# Red_Buggy_2015.net
KiCad netlist of a schematic drawn in EAGLE
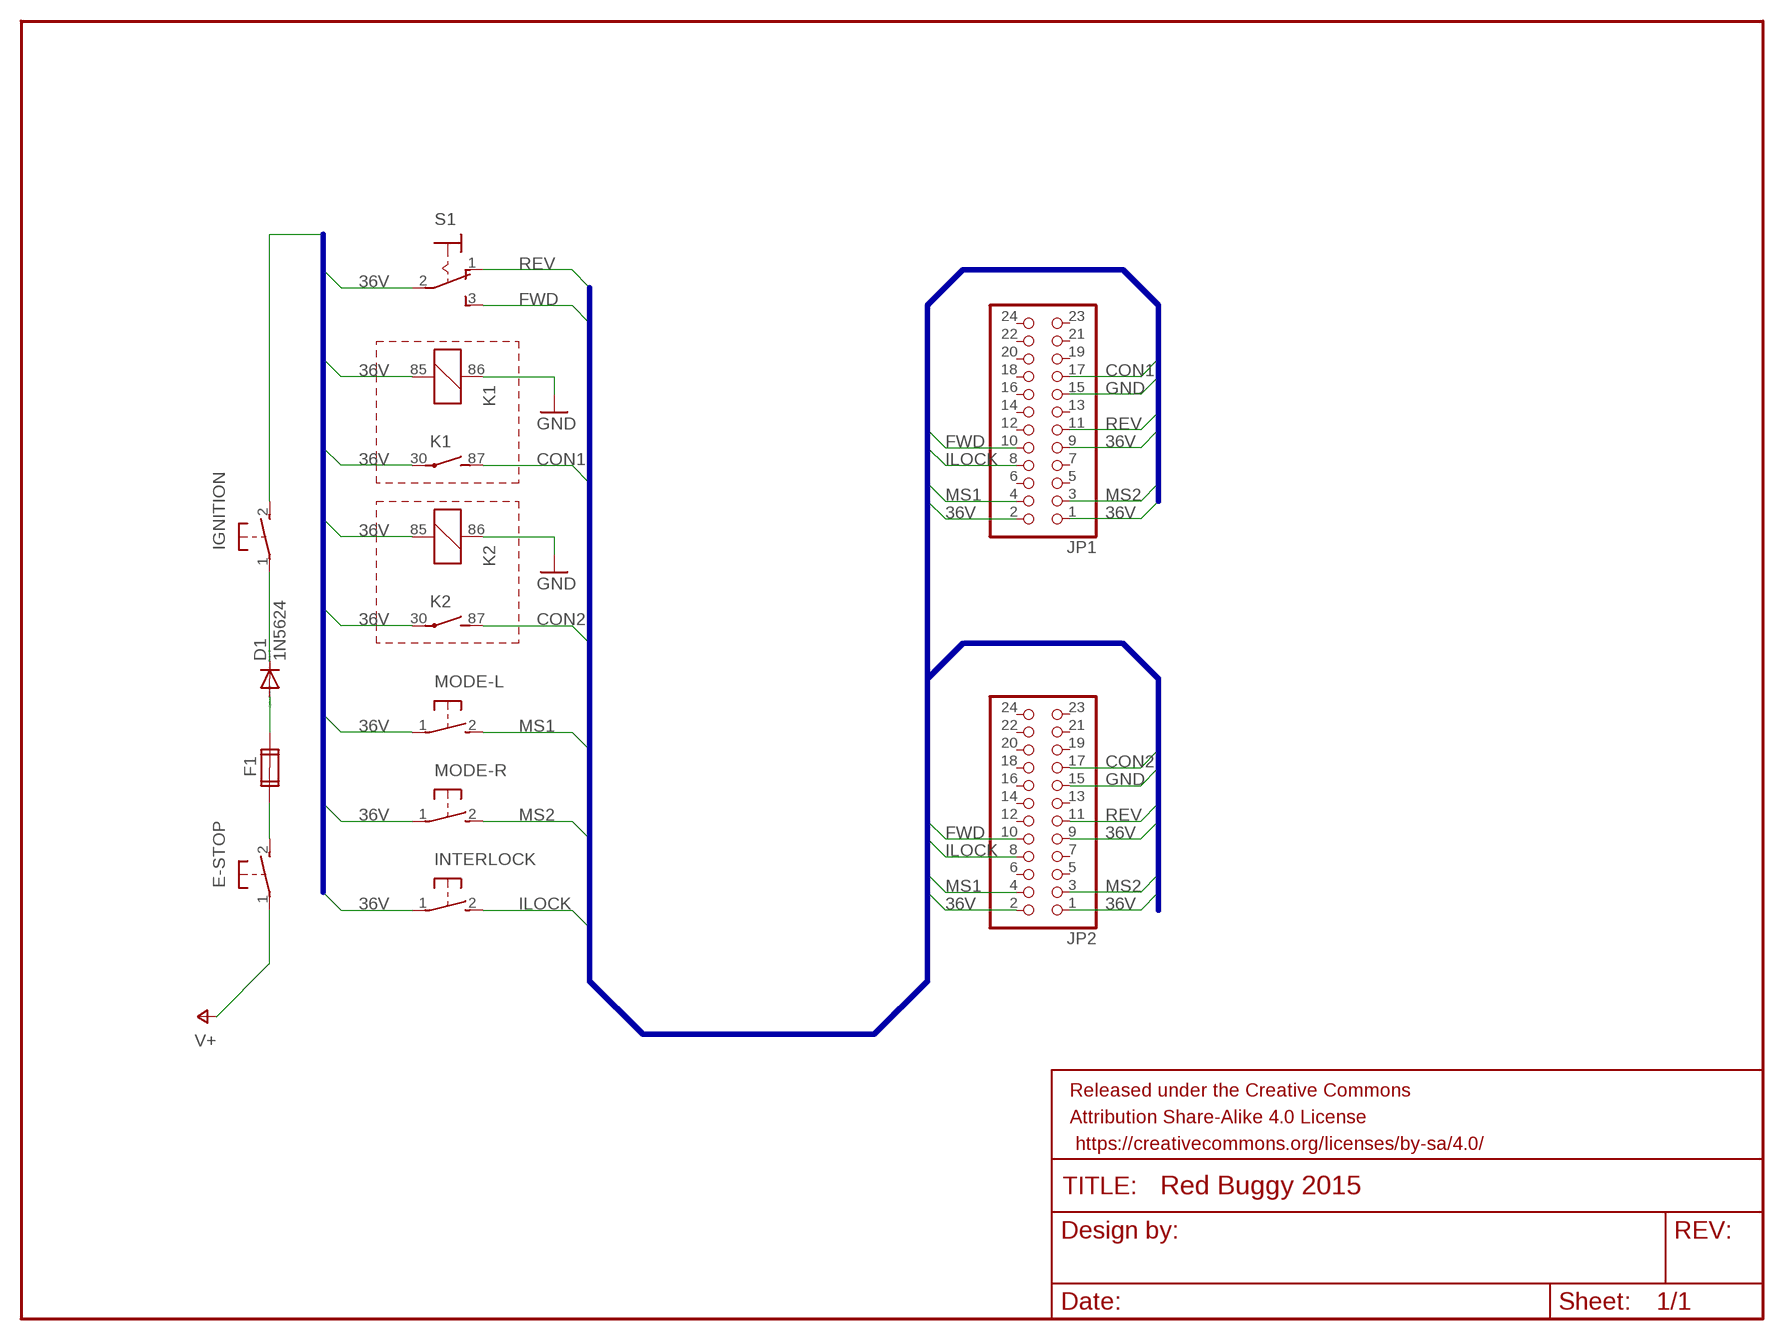
[diagram p0: schematic, sheet 1]

(export (version "E")
  (design (tool "Eeschema 10.0.6"))
  (components
    (comp (ref "D1")
      (value "1N5624")
      (footprint "eagle-import:DO201-15")
      (libsource (lib "eagle-import") (part "1N5624"))
    )
    (comp (ref "E-STOP")
      (value "31-XX")
      (footprint "eagle-import:B3F-31XX")
      (libsource (lib "eagle-import") (part "31-XX"))
    )
    (comp (ref "F1")
      (value "FUSE2P")
      (footprint "eagle-import:FUSE1")
      (libsource (lib "eagle-import") (part "FUSE2P"))
    )
    (comp (ref "FRAME1")
      (value "FRAME-LETTER")
      (footprint "eagle-import:CREATIVE_COMMONS")
      (libsource (lib "eagle-import") (part "FRAME-LETTER"))
    )
    (comp (ref "IGNITION")
      (value "31-XX")
      (footprint "eagle-import:B3F-31XX")
      (libsource (lib "eagle-import") (part "31-XX"))
    )
    (comp (ref "INTERLOCK")
      (value "31-XX")
      (footprint "eagle-import:B3F-31XX")
      (libsource (lib "eagle-import") (part "31-XX"))
    )
    (comp (ref "JP1")
      (value "PINHD-2X12")
      (footprint "eagle-import:2X12")
      (libsource (lib "eagle-import") (part "PINHD-2X12"))
    )
    (comp (ref "JP2")
      (value "PINHD-2X12")
      (footprint "eagle-import:2X12")
      (libsource (lib "eagle-import") (part "PINHD-2X12"))
    )
    (comp (ref "K1")
      (value "CB1A-P-12V")
      (footprint "eagle-import:CB1")
      (fields (field (name "MF") "AROMAT/ MATSUSHITA"))
      (libsource (lib "eagle-import") (part "CB1A-P-12V"))
    )
    (comp (ref "K2")
      (value "CB1A-P-12V")
      (footprint "eagle-import:CB1")
      (fields (field (name "MF") "AROMAT/ MATSUSHITA"))
      (libsource (lib "eagle-import") (part "CB1A-P-12V"))
    )
    (comp (ref "MODE-L")
      (value "31-XX")
      (footprint "eagle-import:B3F-31XX")
      (libsource (lib "eagle-import") (part "31-XX"))
    )
    (comp (ref "MODE-R")
      (value "31-XX")
      (footprint "eagle-import:B3F-31XX")
      (libsource (lib "eagle-import") (part "31-XX"))
    )
    (comp (ref "S1")
      (value "320-916")
      (footprint "eagle-import:320-916")
      (libsource (lib "eagle-import") (part "320-916"))
    )
  )
  (nets
    (net (code "1") (name "/36V") (class "Default")
      (node (ref "IGNITION") (pin "2") (pinfunction "S_2") (pintype "passive"))
      (node (ref "INTERLOCK") (pin "1") (pinfunction "P_1") (pintype "passive"))
      (node (ref "JP1") (pin "1") (pinfunction "1_1") (pintype "passive"))
      (node (ref "JP1") (pin "2") (pinfunction "2_2") (pintype "passive"))
      (node (ref "JP1") (pin "9") (pinfunction "9_9") (pintype "passive"))
      (node (ref "JP2") (pin "1") (pinfunction "1_1") (pintype "passive"))
      (node (ref "JP2") (pin "2") (pinfunction "2_2") (pintype "passive"))
      (node (ref "JP2") (pin "9") (pinfunction "9_9") (pintype "passive"))
      (node (ref "K1") (pin "30") (pinfunction "P_30") (pintype "passive"))
      (node (ref "K1") (pin "85") (pinfunction "2_85") (pintype "passive"))
      (node (ref "K2") (pin "30") (pinfunction "P_30") (pintype "passive"))
      (node (ref "K2") (pin "85") (pinfunction "2_85") (pintype "passive"))
      (node (ref "MODE-L") (pin "1") (pinfunction "P_1") (pintype "passive"))
      (node (ref "MODE-R") (pin "1") (pinfunction "P_1") (pintype "passive"))
      (node (ref "S1") (pin "2") (pinfunction "P_2") (pintype "passive"))
    )
    (net (code "2") (name "/CON1") (class "Default")
      (node (ref "JP1") (pin "17") (pinfunction "17_17") (pintype "passive"))
      (node (ref "K1") (pin "87") (pinfunction "S_87") (pintype "passive"))
    )
    (net (code "3") (name "/CON2") (class "Default")
      (node (ref "JP2") (pin "17") (pinfunction "17_17") (pintype "passive"))
      (node (ref "K2") (pin "87") (pinfunction "S_87") (pintype "passive"))
    )
    (net (code "4") (name "/FWD") (class "Default")
      (node (ref "JP1") (pin "10") (pinfunction "10_10") (pintype "passive"))
      (node (ref "JP2") (pin "10") (pinfunction "10_10") (pintype "passive"))
      (node (ref "S1") (pin "3") (pinfunction "S_3") (pintype "passive"))
    )
    (net (code "5") (name "/ILOCK") (class "Default")
      (node (ref "INTERLOCK") (pin "2") (pinfunction "S_2") (pintype "passive"))
      (node (ref "JP1") (pin "8") (pinfunction "8_8") (pintype "passive"))
      (node (ref "JP2") (pin "8") (pinfunction "8_8") (pintype "passive"))
    )
    (net (code "6") (name "/MS1") (class "Default")
      (node (ref "JP1") (pin "4") (pinfunction "4_4") (pintype "passive"))
      (node (ref "JP2") (pin "4") (pinfunction "4_4") (pintype "passive"))
      (node (ref "MODE-L") (pin "2") (pinfunction "S_2") (pintype "passive"))
    )
    (net (code "7") (name "/MS2") (class "Default")
      (node (ref "JP1") (pin "3") (pinfunction "3_3") (pintype "passive"))
      (node (ref "JP2") (pin "3") (pinfunction "3_3") (pintype "passive"))
      (node (ref "MODE-R") (pin "2") (pinfunction "S_2") (pintype "passive"))
    )
    (net (code "8") (name "/REV") (class "Default")
      (node (ref "JP1") (pin "11") (pinfunction "11_11") (pintype "passive"))
      (node (ref "JP2") (pin "11") (pinfunction "11_11") (pintype "passive"))
      (node (ref "S1") (pin "1") (pinfunction "O_1") (pintype "passive"))
    )
    (net (code "9") (name "GND") (class "Default")
      (node (ref "JP1") (pin "15") (pinfunction "15_15") (pintype "passive"))
      (node (ref "JP2") (pin "15") (pinfunction "15_15") (pintype "passive"))
      (node (ref "K1") (pin "86") (pinfunction "1_86") (pintype "passive"))
      (node (ref "K2") (pin "86") (pinfunction "1_86") (pintype "passive"))
    )
    (net (code "10") (name "Net-(D1-PadA)") (class "Default")
      (node (ref "D1") (pin "A") (pinfunction "A_A") (pintype "passive"))
      (node (ref "F1") (pin "2A") (pinfunction "2A_2A") (pintype "passive"))
    )
    (net (code "11") (name "Net-(E-STOP-S)") (class "Default")
      (node (ref "E-STOP") (pin "2") (pinfunction "S_2") (pintype "passive"))
      (node (ref "F1") (pin "1A") (pinfunction "1A_1A") (pintype "passive"))
    )
    (net (code "12") (name "Net-(IGNITION-P)") (class "Default")
      (node (ref "D1") (pin "C") (pinfunction "C_C") (pintype "passive"))
      (node (ref "IGNITION") (pin "1") (pinfunction "P_1") (pintype "passive"))
    )
    (net (code "13") (name "V+") (class "Default")
      (node (ref "E-STOP") (pin "1") (pinfunction "P_1") (pintype "passive"))
    )
    (net (code "14") (name "unconnected-(F1-Pad1B)") (class "Default")
      (node (ref "F1") (pin "1B") (pinfunction "1B_1B") (pintype "passive"))
    )
    (net (code "15") (name "unconnected-(F1-Pad2B)") (class "Default")
      (node (ref "F1") (pin "2B") (pinfunction "2B_2B") (pintype "passive"))
    )
    (net (code "16") (name "unconnected-(JP1-Pad5)") (class "Default")
      (node (ref "JP1") (pin "5") (pinfunction "5_5") (pintype "passive"))
    )
    (net (code "17") (name "unconnected-(JP1-Pad6)") (class "Default")
      (node (ref "JP1") (pin "6") (pinfunction "6_6") (pintype "passive"))
    )
    (net (code "18") (name "unconnected-(JP1-Pad7)") (class "Default")
      (node (ref "JP1") (pin "7") (pinfunction "7_7") (pintype "passive"))
    )
    (net (code "19") (name "unconnected-(JP1-Pad12)") (class "Default")
      (node (ref "JP1") (pin "12") (pinfunction "12_12") (pintype "passive"))
    )
    (net (code "20") (name "unconnected-(JP1-Pad13)") (class "Default")
      (node (ref "JP1") (pin "13") (pinfunction "13_13") (pintype "passive"))
    )
    (net (code "21") (name "unconnected-(JP1-Pad14)") (class "Default")
      (node (ref "JP1") (pin "14") (pinfunction "14_14") (pintype "passive"))
    )
    (net (code "22") (name "unconnected-(JP1-Pad16)") (class "Default")
      (node (ref "JP1") (pin "16") (pinfunction "16_16") (pintype "passive"))
    )
    (net (code "23") (name "unconnected-(JP1-Pad18)") (class "Default")
      (node (ref "JP1") (pin "18") (pinfunction "18_18") (pintype "passive"))
    )
    (net (code "24") (name "unconnected-(JP1-Pad19)") (class "Default")
      (node (ref "JP1") (pin "19") (pinfunction "19_19") (pintype "passive"))
    )
    (net (code "25") (name "unconnected-(JP1-Pad20)") (class "Default")
      (node (ref "JP1") (pin "20") (pinfunction "20_20") (pintype "passive"))
    )
    (net (code "26") (name "unconnected-(JP1-Pad21)") (class "Default")
      (node (ref "JP1") (pin "21") (pinfunction "21_21") (pintype "passive"))
    )
    (net (code "27") (name "unconnected-(JP1-Pad22)") (class "Default")
      (node (ref "JP1") (pin "22") (pinfunction "22_22") (pintype "passive"))
    )
    (net (code "28") (name "unconnected-(JP1-Pad23)") (class "Default")
      (node (ref "JP1") (pin "23") (pinfunction "23_23") (pintype "passive"))
    )
    (net (code "29") (name "unconnected-(JP1-Pad24)") (class "Default")
      (node (ref "JP1") (pin "24") (pinfunction "24_24") (pintype "passive"))
    )
    (net (code "30") (name "unconnected-(JP2-Pad5)") (class "Default")
      (node (ref "JP2") (pin "5") (pinfunction "5_5") (pintype "passive"))
    )
    (net (code "31") (name "unconnected-(JP2-Pad6)") (class "Default")
      (node (ref "JP2") (pin "6") (pinfunction "6_6") (pintype "passive"))
    )
    (net (code "32") (name "unconnected-(JP2-Pad7)") (class "Default")
      (node (ref "JP2") (pin "7") (pinfunction "7_7") (pintype "passive"))
    )
    (net (code "33") (name "unconnected-(JP2-Pad12)") (class "Default")
      (node (ref "JP2") (pin "12") (pinfunction "12_12") (pintype "passive"))
    )
    (net (code "34") (name "unconnected-(JP2-Pad13)") (class "Default")
      (node (ref "JP2") (pin "13") (pinfunction "13_13") (pintype "passive"))
    )
    (net (code "35") (name "unconnected-(JP2-Pad14)") (class "Default")
      (node (ref "JP2") (pin "14") (pinfunction "14_14") (pintype "passive"))
    )
    (net (code "36") (name "unconnected-(JP2-Pad16)") (class "Default")
      (node (ref "JP2") (pin "16") (pinfunction "16_16") (pintype "passive"))
    )
    (net (code "37") (name "unconnected-(JP2-Pad18)") (class "Default")
      (node (ref "JP2") (pin "18") (pinfunction "18_18") (pintype "passive"))
    )
    (net (code "38") (name "unconnected-(JP2-Pad19)") (class "Default")
      (node (ref "JP2") (pin "19") (pinfunction "19_19") (pintype "passive"))
    )
    (net (code "39") (name "unconnected-(JP2-Pad20)") (class "Default")
      (node (ref "JP2") (pin "20") (pinfunction "20_20") (pintype "passive"))
    )
    (net (code "40") (name "unconnected-(JP2-Pad21)") (class "Default")
      (node (ref "JP2") (pin "21") (pinfunction "21_21") (pintype "passive"))
    )
    (net (code "41") (name "unconnected-(JP2-Pad22)") (class "Default")
      (node (ref "JP2") (pin "22") (pinfunction "22_22") (pintype "passive"))
    )
    (net (code "42") (name "unconnected-(JP2-Pad23)") (class "Default")
      (node (ref "JP2") (pin "23") (pinfunction "23_23") (pintype "passive"))
    )
    (net (code "43") (name "unconnected-(JP2-Pad24)") (class "Default")
      (node (ref "JP2") (pin "24") (pinfunction "24_24") (pintype "passive"))
    )
  )
)
